# Motor.net
KiCad netlist of a schematic drawn in Altium Designer
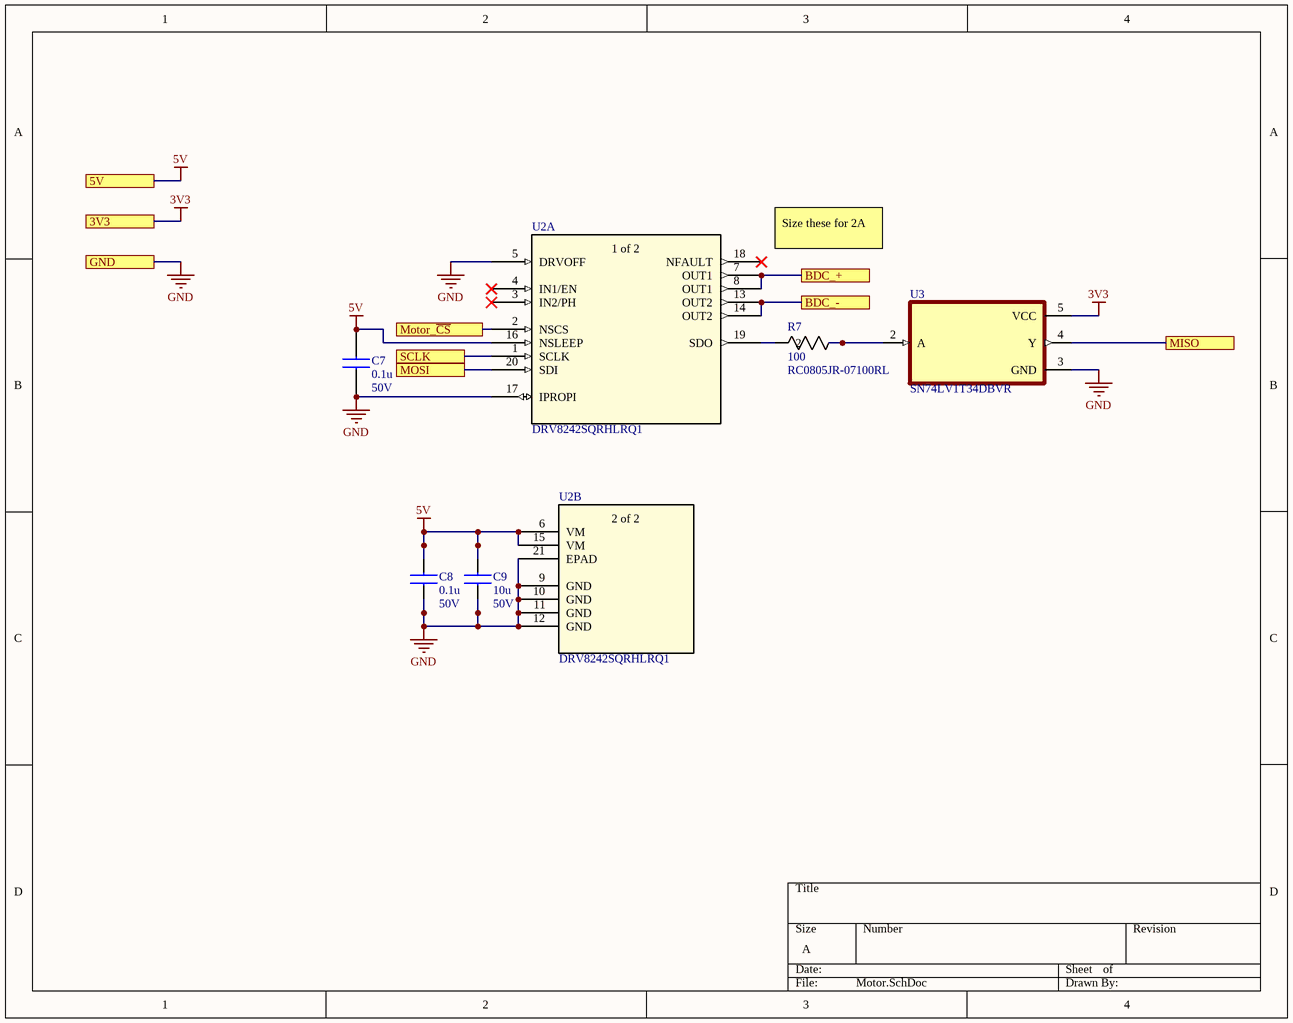
[diagram p0: Motor.SchDoc]

(export (version "E")
  (design (tool "Eeschema 10.0.6"))
  (components
    (comp (ref "C7")
      (value "0.1u")
      (footprint "CAPC2012X145N")
      (description "Multilayer Ceramic Chip Capacitors, Capacitance=0.1u")
      (fields
        (field (name "MANUFACTURER_PART_NUMBER") "KAM21BR71H104JM")
        (field (name "RATED VOLTAGE") "50V")
      )
      (libsource (lib "Caps") (part "KAM21BR71H104JM"))
    )
    (comp (ref "C8")
      (value "0.1u")
      (footprint "CAPC2012X145N")
      (description "Multilayer Ceramic Chip Capacitors, Capacitance=0.1u")
      (fields
        (field (name "MANUFACTURER_PART_NUMBER") "KAM21BR71H104JM")
        (field (name "RATED VOLTAGE") "50V")
      )
      (libsource (lib "Caps") (part "KAM21BR71H104JM"))
    )
    (comp (ref "C9")
      (value "10u")
      (footprint "CAPC2012X145N")
      (description "Multilayer Ceramic Chip Capacitors, Capacitance=10?F, LxWxT:2x1.25x1.25mm")
      (fields
        (field (name "MOUSER PART NUMBER") "810-C2012X5R1H106K12")
        (field (name "MANUFACTURER_PART_NUMBER") "C2012X5R1H106K125AC")
        (field (name "RATED VOLTAGE") "50V")
      )
      (libsource (lib "Caps") (part "C2012X5R1H106K125AC"))
    )
    (comp (ref "R7")
      (value "RC0805JR-07100RL")
      (footprint "RC0805N_YAG")
      (description "RES 0805 100 5% 1/8W")
      (fields (field (name "TOLERANCE") "5%") (field (name "ALTIUM_VALUE") "100"))
      (libsource (lib "Resistors") (part "RC0805JR-07100RL"))
    )
    (comp (ref "U2")
      (value "DRV8242SQRHLRQ1")
      (footprint "VQFN20_RHL_TEX")
      (fields (field (name "COPYRIGHT") "Copyright (C) 2025 Ultra Librarian. All rights reserved."))
      (libsource (lib "DRV8242SQRHLRQ1") (part "DRV8242SQRHLRQ1"))
    )
    (comp (ref "U3")
      (value "SN74LV1T34DBVR")
      (footprint "SOT95P280X145-5N")
      (description "Single Power Supply BUFFER Logic Level Shifter (no enable)")
      (fields (field (name "MF") "Texas Instruments"))
      (libsource (lib "SN74LV1T34DBVR") (part "SN74LV1T34DBVR"))
    )
  )
  (nets
    (net (code "1") (name "/BDC_+") (class "Default")
      (node (ref "U2") (pin "7") (pinfunction "OUT1_7") (pintype "output"))
      (node (ref "U2") (pin "8") (pinfunction "OUT1_8") (pintype "output"))
    )
    (net (code "2") (name "/BDC_-") (class "Default")
      (node (ref "U2") (pin "13") (pinfunction "OUT2_13") (pintype "output"))
      (node (ref "U2") (pin "14") (pinfunction "OUT2_14") (pintype "output"))
    )
    (net (code "3") (name "/MISO") (class "Default")
      (node (ref "U3") (pin "4") (pinfunction "Y_4") (pintype "output"))
    )
    (net (code "4") (name "/MOSI") (class "Default")
      (node (ref "U2") (pin "20") (pinfunction "SDI_20") (pintype "input"))
    )
    (net (code "5") (name "/Motor_~{CS}") (class "Default")
      (node (ref "U2") (pin "2") (pinfunction "NSCS_2") (pintype "input"))
    )
    (net (code "6") (name "/SCLK") (class "Default")
      (node (ref "U2") (pin "1") (pinfunction "SCLK_1") (pintype "input"))
    )
    (net (code "7") (name "3V3") (class "Default")
      (node (ref "U3") (pin "5") (pinfunction "VCC_5") (pintype "power_in"))
    )
    (net (code "8") (name "5V") (class "Default")
      (node (ref "C7") (pin "2") (pinfunction "2_2") (pintype "passive"))
      (node (ref "C8") (pin "2") (pinfunction "2_2") (pintype "passive"))
      (node (ref "C9") (pin "2") (pinfunction "2_2") (pintype "passive"))
      (node (ref "U2") (pin "15") (pinfunction "VM_15") (pintype "power_in"))
      (node (ref "U2") (pin "16") (pinfunction "NSLEEP_16") (pintype "input"))
      (node (ref "U2") (pin "6") (pinfunction "VM_6") (pintype "power_in"))
    )
    (net (code "9") (name "GND") (class "Default")
      (node (ref "C7") (pin "1") (pinfunction "1_1") (pintype "passive"))
      (node (ref "C8") (pin "1") (pinfunction "1_1") (pintype "passive"))
      (node (ref "C9") (pin "1") (pinfunction "1_1") (pintype "passive"))
      (node (ref "U2") (pin "10") (pinfunction "GND_10") (pintype "power_in"))
      (node (ref "U2") (pin "11") (pinfunction "GND_11") (pintype "power_in"))
      (node (ref "U2") (pin "12") (pinfunction "GND_12") (pintype "power_in"))
      (node (ref "U2") (pin "17") (pinfunction "IPROPI_17") (pintype "bidirectional"))
      (node (ref "U2") (pin "21") (pinfunction "EPAD_21") (pintype "power_in"))
      (node (ref "U2") (pin "5") (pinfunction "DRVOFF_5") (pintype "input"))
      (node (ref "U2") (pin "9") (pinfunction "GND_9") (pintype "power_in"))
      (node (ref "U3") (pin "3") (pinfunction "GND_3") (pintype "power_in"))
    )
    (net (code "10") (name "Net-(U2A-SDO)") (class "Default")
      (node (ref "R7") (pin "2") (pinfunction "2_2") (pintype "passive"))
      (node (ref "U2") (pin "19") (pinfunction "SDO_19") (pintype "output"))
    )
    (net (code "11") (name "Net-(U3-A)") (class "Default")
      (node (ref "R7") (pin "1") (pinfunction "1_1") (pintype "passive"))
      (node (ref "U3") (pin "2") (pinfunction "A_2") (pintype "input"))
    )
    (net (code "12") (name "unconnected-(U2A-IN1{slash}EN-Pad4)") (class "Default")
      (node (ref "U2") (pin "4") (pinfunction "IN1/EN_4") (pintype "input+no_connect"))
    )
    (net (code "13") (name "unconnected-(U2A-IN2{slash}PH-Pad3)") (class "Default")
      (node (ref "U2") (pin "3") (pinfunction "IN2/PH_3") (pintype "input+no_connect"))
    )
    (net (code "14") (name "unconnected-(U2A-NFAULT-Pad18)") (class "Default")
      (node (ref "U2") (pin "18") (pinfunction "NFAULT_18") (pintype "output+no_connect"))
    )
  )
)
